# SAMA7D65_MPU.net
KiCad netlist of a schematic drawn in Altium Designer
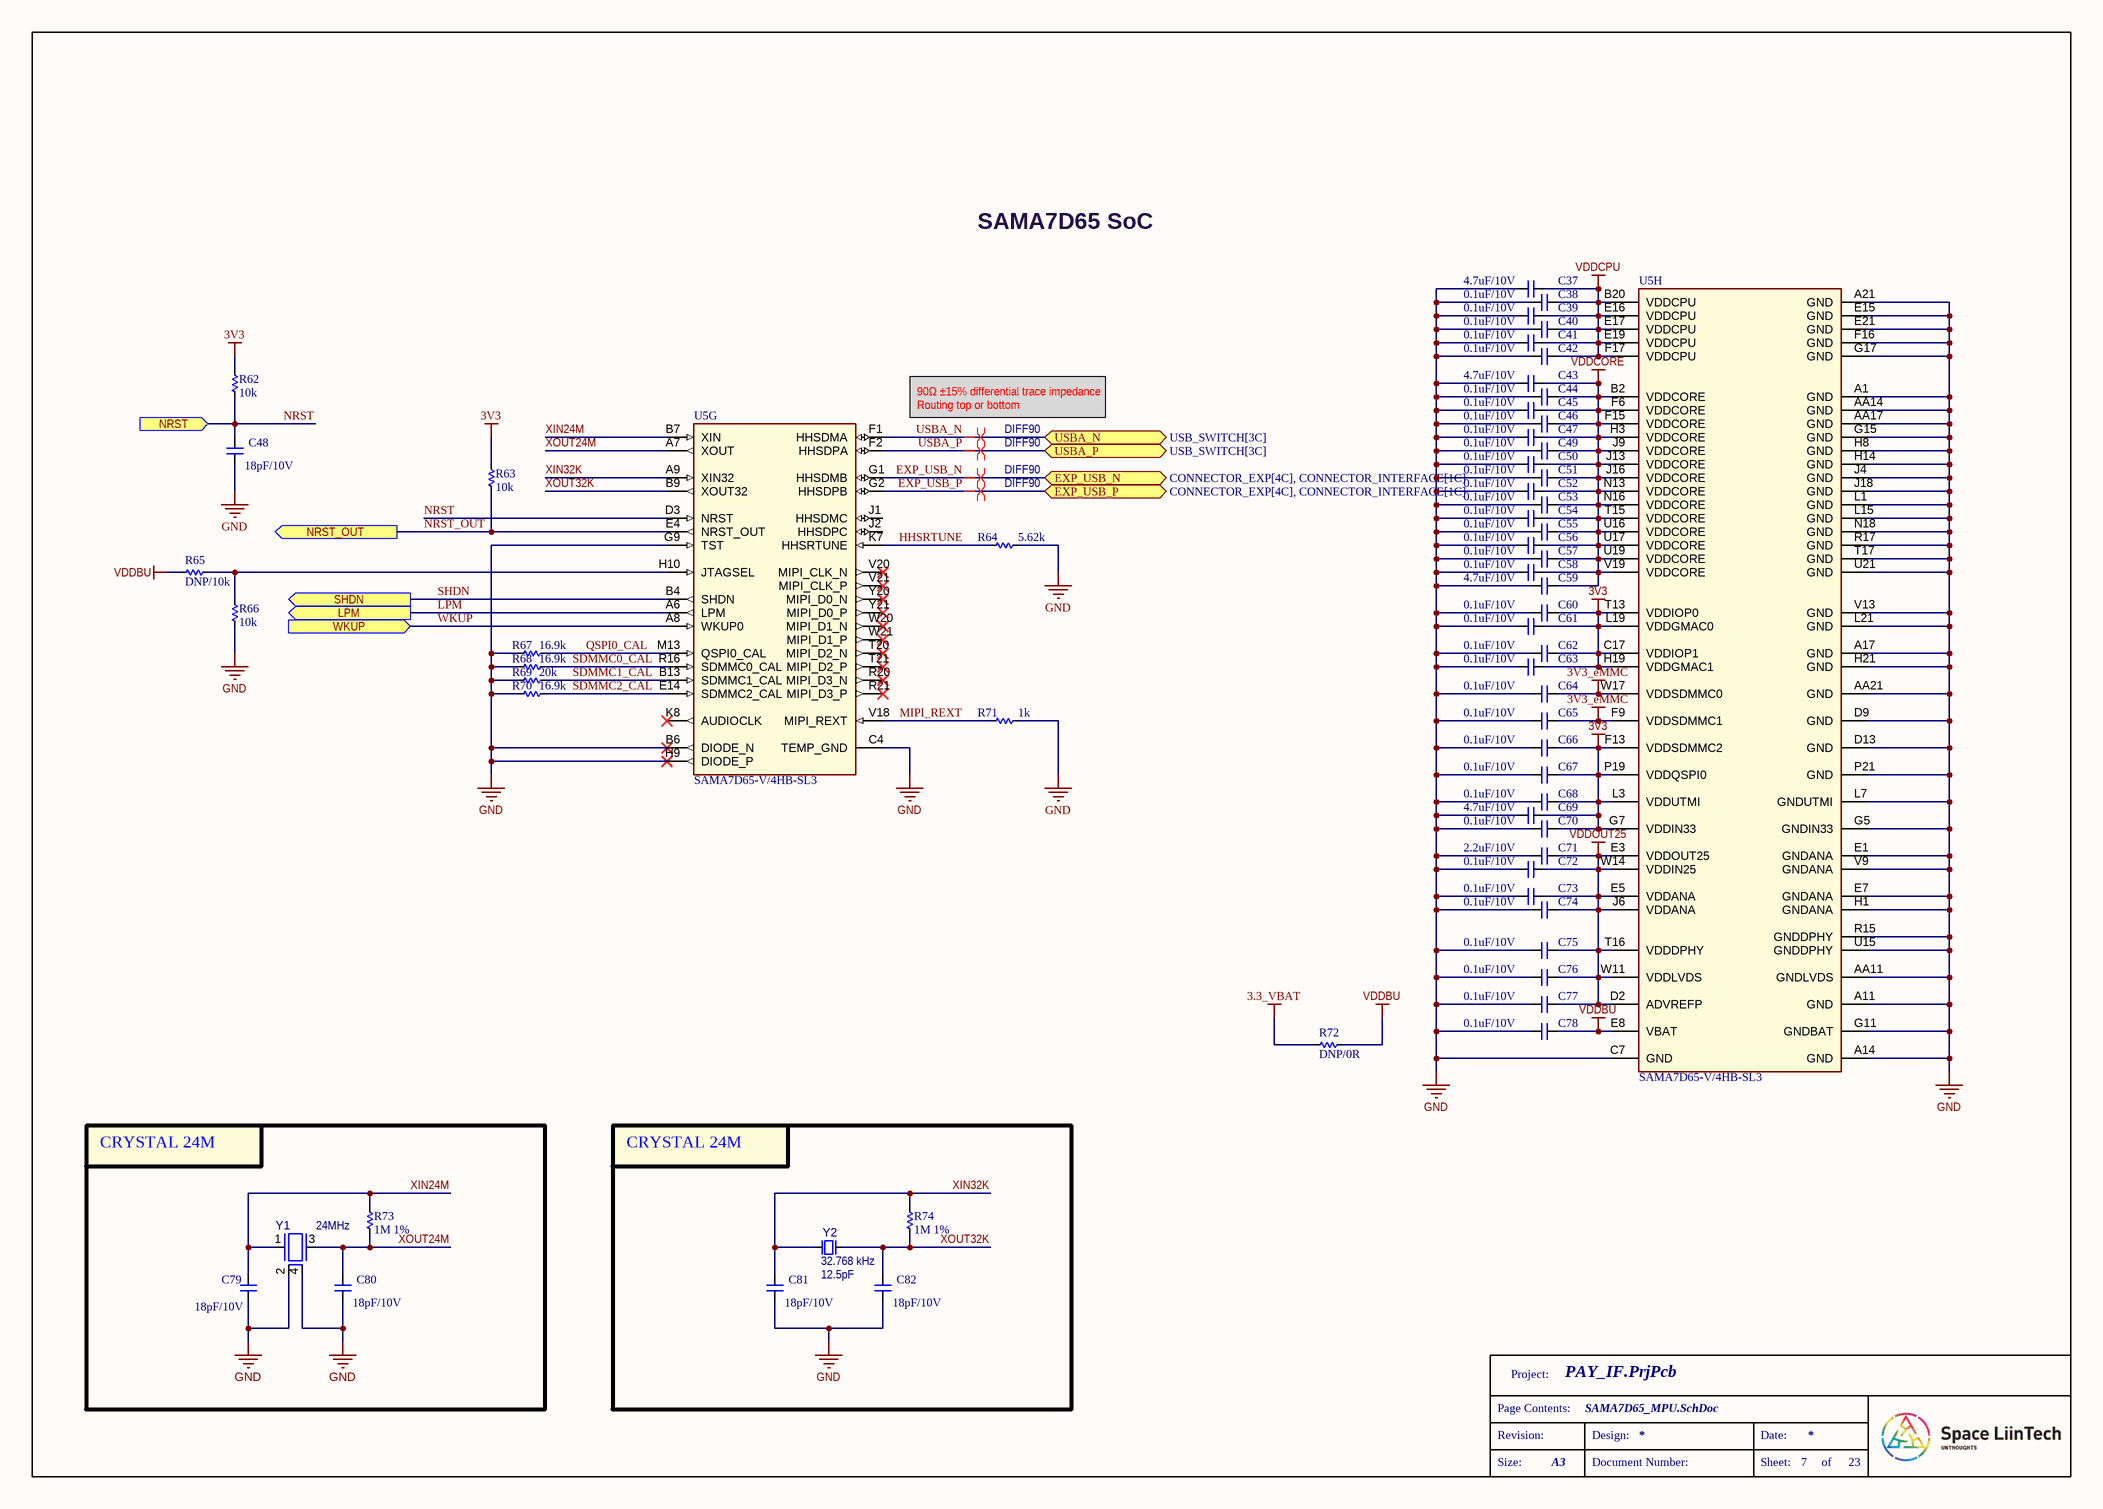
[diagram p0: SAMA7D65_MPU.SchDoc]

(export (version "E")
  (design (tool "Eeschema 10.0.6"))
  (components
    (comp (ref "C37")
      (value "4.7uF/10V")
      (footprint "CAP_C_1005X50_L")
      (description "CAP CHIP")
      (libsource (lib "IFBschelib") (part "_CAP_C_2"))
    )
    (comp (ref "C38")
      (value "0.1uF/10V")
      (footprint "CAP_C_0603x30")
      (description "CAP CHIP")
      (libsource (lib "IFBschelib") (part "_CAP_C_2"))
    )
    (comp (ref "C39")
      (value "0.1uF/10V")
      (footprint "CAP_C_0603x30")
      (description "CAP CHIP")
      (libsource (lib "IFBschelib") (part "_CAP_C_2"))
    )
    (comp (ref "C40")
      (value "0.1uF/10V")
      (footprint "CAP_C_0603x30")
      (description "CAP CHIP")
      (libsource (lib "IFBschelib") (part "_CAP_C_2"))
    )
    (comp (ref "C41")
      (value "0.1uF/10V")
      (footprint "CAP_C_0603x30")
      (description "CAP CHIP")
      (libsource (lib "IFBschelib") (part "_CAP_C_2"))
    )
    (comp (ref "C42")
      (value "0.1uF/10V")
      (footprint "CAP_C_0603x30")
      (description "CAP CHIP")
      (libsource (lib "IFBschelib") (part "_CAP_C_2"))
    )
    (comp (ref "C43")
      (value "4.7uF/10V")
      (footprint "CAP_C_1005X50_L")
      (description "CAP CHIP")
      (libsource (lib "IFBschelib") (part "_CAP_C_2"))
    )
    (comp (ref "C44")
      (value "0.1uF/10V")
      (footprint "CAP_C_0603x30")
      (description "CAP CHIP")
      (libsource (lib "IFBschelib") (part "_CAP_C_2"))
    )
    (comp (ref "C45")
      (value "0.1uF/10V")
      (footprint "CAP_C_0603x30")
      (description "CAP CHIP")
      (libsource (lib "IFBschelib") (part "_CAP_C_2"))
    )
    (comp (ref "C46")
      (value "0.1uF/10V")
      (footprint "CAP_C_0603x30")
      (description "CAP CHIP")
      (libsource (lib "IFBschelib") (part "_CAP_C_2"))
    )
    (comp (ref "C47")
      (value "0.1uF/10V")
      (footprint "CAP_C_0603x30")
      (description "CAP CHIP")
      (libsource (lib "IFBschelib") (part "_CAP_C_2"))
    )
    (comp (ref "C48")
      (value "18pF/10V")
      (footprint "CAP_C_0603x30")
      (description "CAP CHIP")
      (libsource (lib "IFBschelib") (part "_CAP_C_2"))
    )
    (comp (ref "C49")
      (value "0.1uF/10V")
      (footprint "CAP_C_0603x30")
      (description "CAP CHIP")
      (libsource (lib "IFBschelib") (part "_CAP_C_2"))
    )
    (comp (ref "C50")
      (value "0.1uF/10V")
      (footprint "CAP_C_0603x30")
      (description "CAP CHIP")
      (libsource (lib "IFBschelib") (part "_CAP_C_2"))
    )
    (comp (ref "C51")
      (value "0.1uF/10V")
      (footprint "CAP_C_0603x30")
      (description "CAP CHIP")
      (libsource (lib "IFBschelib") (part "_CAP_C_2"))
    )
    (comp (ref "C52")
      (value "0.1uF/10V")
      (footprint "CAP_C_0603x30")
      (description "CAP CHIP")
      (libsource (lib "IFBschelib") (part "_CAP_C_2"))
    )
    (comp (ref "C53")
      (value "0.1uF/10V")
      (footprint "CAP_C_0603x30")
      (description "CAP CHIP")
      (libsource (lib "IFBschelib") (part "_CAP_C_2"))
    )
    (comp (ref "C54")
      (value "0.1uF/10V")
      (footprint "CAP_C_0603x30")
      (description "CAP CHIP")
      (libsource (lib "IFBschelib") (part "_CAP_C_2"))
    )
    (comp (ref "C55")
      (value "0.1uF/10V")
      (footprint "CAP_C_0603x30")
      (description "CAP CHIP")
      (libsource (lib "IFBschelib") (part "_CAP_C_2"))
    )
    (comp (ref "C56")
      (value "0.1uF/10V")
      (footprint "CAP_C_0603x30")
      (description "CAP CHIP")
      (libsource (lib "IFBschelib") (part "_CAP_C_2"))
    )
    (comp (ref "C57")
      (value "0.1uF/10V")
      (footprint "CAP_C_0603x30")
      (description "CAP CHIP")
      (libsource (lib "IFBschelib") (part "_CAP_C_2"))
    )
    (comp (ref "C58")
      (value "0.1uF/10V")
      (footprint "CAP_C_0603x30")
      (description "CAP CHIP")
      (libsource (lib "IFBschelib") (part "_CAP_C_2"))
    )
    (comp (ref "C59")
      (value "4.7uF/10V")
      (footprint "CAP_C_1005X50_L")
      (description "CAP CHIP")
      (libsource (lib "IFBschelib") (part "_CAP_C_2"))
    )
    (comp (ref "C60")
      (value "0.1uF/10V")
      (footprint "CAP_C_0603x30")
      (description "CAP CHIP")
      (libsource (lib "IFBschelib") (part "_CAP_C_2"))
    )
    (comp (ref "C61")
      (value "0.1uF/10V")
      (footprint "CAP_C_0603x30")
      (description "CAP CHIP")
      (libsource (lib "IFBschelib") (part "_CAP_C_2"))
    )
    (comp (ref "C62")
      (value "0.1uF/10V")
      (footprint "CAP_C_0603x30")
      (description "CAP CHIP")
      (libsource (lib "IFBschelib") (part "_CAP_C_2"))
    )
    (comp (ref "C63")
      (value "0.1uF/10V")
      (footprint "CAP_C_0603x30")
      (description "CAP CHIP")
      (libsource (lib "IFBschelib") (part "_CAP_C_2"))
    )
    (comp (ref "C64")
      (value "0.1uF/10V")
      (footprint "CAP_C_0603x30")
      (description "CAP CHIP")
      (libsource (lib "IFBschelib") (part "_CAP_C_2"))
    )
    (comp (ref "C65")
      (value "0.1uF/10V")
      (footprint "CAP_C_0603x30")
      (description "CAP CHIP")
      (libsource (lib "IFBschelib") (part "_CAP_C_2"))
    )
    (comp (ref "C66")
      (value "0.1uF/10V")
      (footprint "CAP_C_0603x30")
      (description "CAP CHIP")
      (libsource (lib "IFBschelib") (part "_CAP_C_2"))
    )
    (comp (ref "C67")
      (value "0.1uF/10V")
      (footprint "CAP_C_0603x30")
      (description "CAP CHIP")
      (libsource (lib "IFBschelib") (part "_CAP_C_2"))
    )
    (comp (ref "C68")
      (value "0.1uF/10V")
      (footprint "CAP_C_0603x30")
      (description "CAP CHIP")
      (libsource (lib "IFBschelib") (part "_CAP_C_2"))
    )
    (comp (ref "C69")
      (value "4.7uF/10V")
      (footprint "CAP_C_1005X50_L")
      (description "CAP CHIP")
      (libsource (lib "IFBschelib") (part "_CAP_C_2"))
    )
    (comp (ref "C70")
      (value "0.1uF/10V")
      (footprint "CAP_C_0603x30")
      (description "CAP CHIP")
      (libsource (lib "IFBschelib") (part "_CAP_C_2"))
    )
    (comp (ref "C71")
      (value "2.2uF/10V")
      (footprint "CAP_C_1005X50_L")
      (description "CAP CHIP")
      (libsource (lib "IFBschelib") (part "_CAP_C_2"))
    )
    (comp (ref "C72")
      (value "0.1uF/10V")
      (footprint "CAP_C_0603x30")
      (description "CAP CHIP")
      (libsource (lib "IFBschelib") (part "_CAP_C_2"))
    )
    (comp (ref "C73")
      (value "0.1uF/10V")
      (footprint "CAP_C_0603x30")
      (description "CAP CHIP")
      (libsource (lib "IFBschelib") (part "_CAP_C_2"))
    )
    (comp (ref "C74")
      (value "0.1uF/10V")
      (footprint "CAP_C_0603x30")
      (description "CAP CHIP")
      (libsource (lib "IFBschelib") (part "_CAP_C_2"))
    )
    (comp (ref "C75")
      (value "0.1uF/10V")
      (footprint "CAP_C_0603x30")
      (description "CAP CHIP")
      (libsource (lib "IFBschelib") (part "_CAP_C_2"))
    )
    (comp (ref "C76")
      (value "0.1uF/10V")
      (footprint "CAP_C_0603x30")
      (description "CAP CHIP")
      (libsource (lib "IFBschelib") (part "_CAP_C_2"))
    )
    (comp (ref "C77")
      (value "0.1uF/10V")
      (footprint "CAP_C_0603x30")
      (description "CAP CHIP")
      (libsource (lib "IFBschelib") (part "_CAP_C_2"))
    )
    (comp (ref "C78")
      (value "0.1uF/10V")
      (footprint "CAP_C_0603x30")
      (description "CAP CHIP")
      (libsource (lib "IFBschelib") (part "_CAP_C_2"))
    )
    (comp (ref "C79")
      (value "18pF/10V")
      (footprint "CAP_C_0603x30")
      (description "CAP CHIP")
      (libsource (lib "IFBschelib") (part "_CAP_C_2"))
    )
    (comp (ref "C80")
      (value "18pF/10V")
      (footprint "CAP_C_0603x30")
      (description "CAP CHIP")
      (libsource (lib "IFBschelib") (part "_CAP_C_2"))
    )
    (comp (ref "C81")
      (value "18pF/10V")
      (footprint "CAP_C_0603x30")
      (description "CAP CHIP")
      (libsource (lib "IFBschelib") (part "_CAP_C_2"))
    )
    (comp (ref "C82")
      (value "18pF/10V")
      (footprint "CAP_C_0603x30")
      (description "CAP CHIP")
      (libsource (lib "IFBschelib") (part "_CAP_C_2"))
    )
    (comp (ref "R62")
      (value "10k")
      (footprint "RES_C_1005x30_L")
      (description "RES")
      (libsource (lib "IFBschelib") (part "_RES_B_2"))
    )
    (comp (ref "R63")
      (value "10k")
      (footprint "RES_C_1005x30_L")
      (description "RES")
      (libsource (lib "IFBschelib") (part "_RES_B_2"))
    )
    (comp (ref "R64")
      (value "5.62k")
      (footprint "RES_C_1005x30_L")
      (description "RES")
      (libsource (lib "IFBschelib") (part "_RES_B_2"))
    )
    (comp (ref "R65")
      (value "DNP/10k")
      (footprint "RES_C_1005x30_L")
      (description "RES")
      (libsource (lib "IFBschelib") (part "_RES_B_2"))
    )
    (comp (ref "R66")
      (value "10k")
      (footprint "RES_C_1005x30_L")
      (description "RES")
      (libsource (lib "IFBschelib") (part "_RES_B_2"))
    )
    (comp (ref "R67")
      (value "16.9k")
      (footprint "RES_C_0603X30")
      (description "RES")
      (libsource (lib "IFBschelib") (part "_RES_B_2"))
    )
    (comp (ref "R68")
      (value "16.9k")
      (footprint "RES_C_0603X30")
      (description "RES")
      (libsource (lib "IFBschelib") (part "_RES_B_2"))
    )
    (comp (ref "R69")
      (value "20k")
      (footprint "RES_C_0603X30")
      (description "RES")
      (libsource (lib "IFBschelib") (part "_RES_B_2"))
    )
    (comp (ref "R70")
      (value "16.9k")
      (footprint "RES_C_0603X30")
      (description "RES")
      (libsource (lib "IFBschelib") (part "_RES_B_2"))
    )
    (comp (ref "R71")
      (value "1k")
      (footprint "RES_C_1005x30_L")
      (description "RES")
      (libsource (lib "IFBschelib") (part "_RES_B_2"))
    )
    (comp (ref "R72")
      (value "DNP/0R")
      (footprint "RES_C_1005x30_L")
      (description "RES")
      (libsource (lib "IFBschelib") (part "_RES_B_2"))
    )
    (comp (ref "R73")
      (value "1M 1%")
      (footprint "RES_C_1005x30_L")
      (description "RES")
      (libsource (lib "IFBschelib") (part "_RES_B_2"))
    )
    (comp (ref "R74")
      (value "1M 1%")
      (footprint "RES_C_1005x30_L")
      (description "RES")
      (libsource (lib "IFBschelib") (part "_RES_B_2"))
    )
    (comp (ref "U5")
      (value "SAMA7D65-V/4HB-SL3")
      (footprint "TFBGA-343_14x14")
      (description "SAMA7D65 MPU 1000MHz Cortex-A7 TFBGA-343")
      (fields (field (name "Comment") "SAMA7D65") (field (name "OWNER") "Ciprian Abramov"))
      (libsource (lib "IFBschelib") (part "SAMA7D65"))
    )
    (comp (ref "Y1")
      (value "24MHz")
      (footprint "XTAL_ECS2401037B2JTNTR")
      (description "CRYSTAL 24 MHZ 10PF SMD")
      (fields
        (field (name "TOLERANCE") "20ppm")
        (field (name "Comment") "Crystal 4 Pins")
        (field (name "OWNER") "Ciprian Abramov")
      )
      (libsource (lib "IFBschelib") (part "ECS-240-10-37B2-JTN-TR"))
    )
    (comp (ref "Y2")
      (value "32.768 kHz")
      (footprint "CRYSTAL_FC-12M_L2.05W1.2H0.6")
      (description "CRYSTAL 32.7680KHZ 12.5PF SMD")
      (fields
        (field (name "TOLERANCE") "20ppm")
        (field (name "LOAD CAPACITANCE") "12.5pF")
        (field (name "Comment") "Crystal 2 Pins")
        (field (name "OWNER") "Dragos Danaila")
      )
      (libsource (lib "IFBschelib") (part "FC-12M 32.7680KA-A3"))
    )
  )
  (nets
    (net (code "1") (name "/EXP_USB_N") (class "Default")
      (node (ref "U5") (pin "G1") (pinfunction "HHSDMB_G1") (pintype "bidirectional"))
    )
    (net (code "2") (name "/EXP_USB_P") (class "Default")
      (node (ref "U5") (pin "G2") (pinfunction "HHSDPB_G2") (pintype "bidirectional"))
    )
    (net (code "3") (name "/HHSRTUNE") (class "Default")
      (node (ref "R64") (pin "1") (pinfunction "1_1") (pintype "passive"))
      (node (ref "U5") (pin "K7") (pinfunction "HHSRTUNE_K7") (pintype "input"))
    )
    (net (code "4") (name "/LPM") (class "Default")
      (node (ref "U5") (pin "A6") (pinfunction "LPM_A6") (pintype "output"))
    )
    (net (code "5") (name "/MIPI_REXT") (class "Default")
      (node (ref "R71") (pin "1") (pinfunction "1_1") (pintype "passive"))
      (node (ref "U5") (pin "V18") (pinfunction "MIPI_REXT_V18") (pintype "input"))
    )
    (net (code "6") (name "/NRST") (class "Default")
      (node (ref "C48") (pin "1") (pinfunction "1_1") (pintype "passive"))
      (node (ref "R62") (pin "2") (pinfunction "2_2") (pintype "passive"))
      (node (ref "U5") (pin "D3") (pinfunction "NRST_D3") (pintype "input"))
    )
    (net (code "7") (name "/NRST_OUT") (class "Default")
      (node (ref "R63") (pin "2") (pinfunction "2_2") (pintype "passive"))
      (node (ref "U5") (pin "E4") (pinfunction "NRST_OUT_E4") (pintype "output"))
    )
    (net (code "8") (name "/QSPI0_CAL") (class "Default")
      (node (ref "R67") (pin "2") (pinfunction "2_2") (pintype "passive"))
      (node (ref "U5") (pin "M13") (pinfunction "QSPI0_CAL_M13") (pintype "input"))
    )
    (net (code "9") (name "/SDMMC0_CAL") (class "Default")
      (node (ref "R68") (pin "2") (pinfunction "2_2") (pintype "passive"))
      (node (ref "U5") (pin "R16") (pinfunction "SDMMC0_CAL_R16") (pintype "input"))
    )
    (net (code "10") (name "/SDMMC1_CAL") (class "Default")
      (node (ref "R69") (pin "2") (pinfunction "2_2") (pintype "passive"))
      (node (ref "U5") (pin "B13") (pinfunction "SDMMC1_CAL_B13") (pintype "input"))
    )
    (net (code "11") (name "/SDMMC2_CAL") (class "Default")
      (node (ref "R70") (pin "2") (pinfunction "2_2") (pintype "passive"))
      (node (ref "U5") (pin "E14") (pinfunction "SDMMC2_CAL_E14") (pintype "input"))
    )
    (net (code "12") (name "/SHDN") (class "Default")
      (node (ref "U5") (pin "B4") (pinfunction "SHDN_B4") (pintype "output"))
    )
    (net (code "13") (name "/USBA_N") (class "Default")
      (node (ref "U5") (pin "F1") (pinfunction "HHSDMA_F1") (pintype "bidirectional"))
    )
    (net (code "14") (name "/USBA_P") (class "Default")
      (node (ref "U5") (pin "F2") (pinfunction "HHSDPA_F2") (pintype "bidirectional"))
    )
    (net (code "15") (name "/WKUP") (class "Default")
      (node (ref "U5") (pin "A8") (pinfunction "WKUP0_A8") (pintype "input"))
    )
    (net (code "16") (name "/XIN24M") (class "Default")
      (node (ref "C79") (pin "1") (pinfunction "1_1") (pintype "passive"))
      (node (ref "R73") (pin "2") (pinfunction "2_2") (pintype "passive"))
      (node (ref "U5") (pin "B7") (pinfunction "XIN_B7") (pintype "input"))
      (node (ref "Y1") (pin "1") (pinfunction "Osc1_1") (pintype "passive"))
    )
    (net (code "17") (name "/XIN32K") (class "Default")
      (node (ref "C81") (pin "1") (pinfunction "1_1") (pintype "passive"))
      (node (ref "R74") (pin "2") (pinfunction "2_2") (pintype "passive"))
      (node (ref "U5") (pin "A9") (pinfunction "XIN32_A9") (pintype "input"))
      (node (ref "Y2") (pin "1") (pinfunction "Osc1_1") (pintype "passive"))
    )
    (net (code "18") (name "/XOUT24M") (class "Default")
      (node (ref "C80") (pin "1") (pinfunction "1_1") (pintype "passive"))
      (node (ref "R73") (pin "1") (pinfunction "1_1") (pintype "passive"))
      (node (ref "U5") (pin "A7") (pinfunction "XOUT_A7") (pintype "output"))
      (node (ref "Y1") (pin "3") (pinfunction "Osc2_3") (pintype "passive"))
    )
    (net (code "19") (name "/XOUT32K") (class "Default")
      (node (ref "C82") (pin "1") (pinfunction "1_1") (pintype "passive"))
      (node (ref "R74") (pin "1") (pinfunction "1_1") (pintype "passive"))
      (node (ref "U5") (pin "B9") (pinfunction "XOUT32_B9") (pintype "output"))
      (node (ref "Y2") (pin "2") (pinfunction "Osc2_2") (pintype "passive"))
    )
    (net (code "20") (name "3.3_VBAT") (class "Default")
      (node (ref "R72") (pin "1") (pinfunction "1_1") (pintype "passive"))
    )
    (net (code "21") (name "3V3") (class "Default")
      (node (ref "C60") (pin "2") (pinfunction "2_2") (pintype "passive"))
      (node (ref "C61") (pin "2") (pinfunction "2_2") (pintype "passive"))
      (node (ref "C62") (pin "2") (pinfunction "2_2") (pintype "passive"))
      (node (ref "C63") (pin "2") (pinfunction "2_2") (pintype "passive"))
      (node (ref "C66") (pin "2") (pinfunction "2_2") (pintype "passive"))
      (node (ref "C67") (pin "2") (pinfunction "2_2") (pintype "passive"))
      (node (ref "C68") (pin "2") (pinfunction "2_2") (pintype "passive"))
      (node (ref "C69") (pin "2") (pinfunction "2_2") (pintype "passive"))
      (node (ref "C70") (pin "2") (pinfunction "2_2") (pintype "passive"))
      (node (ref "R62") (pin "1") (pinfunction "1_1") (pintype "passive"))
      (node (ref "R63") (pin "1") (pinfunction "1_1") (pintype "passive"))
      (node (ref "U5") (pin "C17") (pinfunction "VDDIOP1_C17") (pintype "power_in"))
      (node (ref "U5") (pin "F13") (pinfunction "VDDSDMMC2_F13") (pintype "power_in"))
      (node (ref "U5") (pin "G7") (pinfunction "VDDIN33_G7") (pintype "power_in"))
      (node (ref "U5") (pin "H19") (pinfunction "VDDGMAC1_H19") (pintype "power_in"))
      (node (ref "U5") (pin "L19") (pinfunction "VDDGMAC0_L19") (pintype "power_in"))
      (node (ref "U5") (pin "L3") (pinfunction "VDDUTMI_L3") (pintype "power_in"))
      (node (ref "U5") (pin "P19") (pinfunction "VDDQSPI0_P19") (pintype "power_in"))
      (node (ref "U5") (pin "T13") (pinfunction "VDDIOP0_T13") (pintype "power_in"))
    )
    (net (code "22") (name "3V3_eMMC") (class "Default")
      (node (ref "C64") (pin "2") (pinfunction "2_2") (pintype "passive"))
      (node (ref "C65") (pin "2") (pinfunction "2_2") (pintype "passive"))
      (node (ref "U5") (pin "F9") (pinfunction "VDDSDMMC1_F9") (pintype "power_in"))
      (node (ref "U5") (pin "W17") (pinfunction "VDDSDMMC0_W17") (pintype "power_in"))
    )
    (net (code "23") (name "GND") (class "Default")
      (node (ref "C37") (pin "1") (pinfunction "1_1") (pintype "passive"))
      (node (ref "C38") (pin "1") (pinfunction "1_1") (pintype "passive"))
      (node (ref "C39") (pin "1") (pinfunction "1_1") (pintype "passive"))
      (node (ref "C40") (pin "1") (pinfunction "1_1") (pintype "passive"))
      (node (ref "C41") (pin "1") (pinfunction "1_1") (pintype "passive"))
      (node (ref "C42") (pin "1") (pinfunction "1_1") (pintype "passive"))
      (node (ref "C43") (pin "1") (pinfunction "1_1") (pintype "passive"))
      (node (ref "C44") (pin "1") (pinfunction "1_1") (pintype "passive"))
      (node (ref "C45") (pin "1") (pinfunction "1_1") (pintype "passive"))
      (node (ref "C46") (pin "1") (pinfunction "1_1") (pintype "passive"))
      (node (ref "C47") (pin "1") (pinfunction "1_1") (pintype "passive"))
      (node (ref "C48") (pin "2") (pinfunction "2_2") (pintype "passive"))
      (node (ref "C49") (pin "1") (pinfunction "1_1") (pintype "passive"))
      (node (ref "C50") (pin "1") (pinfunction "1_1") (pintype "passive"))
      (node (ref "C51") (pin "1") (pinfunction "1_1") (pintype "passive"))
      (node (ref "C52") (pin "1") (pinfunction "1_1") (pintype "passive"))
      (node (ref "C53") (pin "1") (pinfunction "1_1") (pintype "passive"))
      (node (ref "C54") (pin "1") (pinfunction "1_1") (pintype "passive"))
      (node (ref "C55") (pin "1") (pinfunction "1_1") (pintype "passive"))
      (node (ref "C56") (pin "1") (pinfunction "1_1") (pintype "passive"))
      (node (ref "C57") (pin "1") (pinfunction "1_1") (pintype "passive"))
      (node (ref "C58") (pin "1") (pinfunction "1_1") (pintype "passive"))
      (node (ref "C59") (pin "1") (pinfunction "1_1") (pintype "passive"))
      (node (ref "C60") (pin "1") (pinfunction "1_1") (pintype "passive"))
      (node (ref "C61") (pin "1") (pinfunction "1_1") (pintype "passive"))
      (node (ref "C62") (pin "1") (pinfunction "1_1") (pintype "passive"))
      (node (ref "C63") (pin "1") (pinfunction "1_1") (pintype "passive"))
      (node (ref "C64") (pin "1") (pinfunction "1_1") (pintype "passive"))
      (node (ref "C65") (pin "1") (pinfunction "1_1") (pintype "passive"))
      (node (ref "C66") (pin "1") (pinfunction "1_1") (pintype "passive"))
      (node (ref "C67") (pin "1") (pinfunction "1_1") (pintype "passive"))
      (node (ref "C68") (pin "1") (pinfunction "1_1") (pintype "passive"))
      (node (ref "C69") (pin "1") (pinfunction "1_1") (pintype "passive"))
      (node (ref "C70") (pin "1") (pinfunction "1_1") (pintype "passive"))
      (node (ref "C71") (pin "1") (pinfunction "1_1") (pintype "passive"))
      (node (ref "C72") (pin "1") (pinfunction "1_1") (pintype "passive"))
      (node (ref "C73") (pin "1") (pinfunction "1_1") (pintype "passive"))
      (node (ref "C74") (pin "1") (pinfunction "1_1") (pintype "passive"))
      (node (ref "C75") (pin "1") (pinfunction "1_1") (pintype "passive"))
      (node (ref "C76") (pin "1") (pinfunction "1_1") (pintype "passive"))
      (node (ref "C77") (pin "1") (pinfunction "1_1") (pintype "passive"))
      (node (ref "C78") (pin "1") (pinfunction "1_1") (pintype "passive"))
      (node (ref "C79") (pin "2") (pinfunction "2_2") (pintype "passive"))
      (node (ref "C80") (pin "2") (pinfunction "2_2") (pintype "passive"))
      (node (ref "C81") (pin "2") (pinfunction "2_2") (pintype "passive"))
      (node (ref "C82") (pin "2") (pinfunction "2_2") (pintype "passive"))
      (node (ref "R64") (pin "2") (pinfunction "2_2") (pintype "passive"))
      (node (ref "R66") (pin "1") (pinfunction "1_1") (pintype "passive"))
      (node (ref "R67") (pin "1") (pinfunction "1_1") (pintype "passive"))
      (node (ref "R68") (pin "1") (pinfunction "1_1") (pintype "passive"))
      (node (ref "R69") (pin "1") (pinfunction "1_1") (pintype "passive"))
      (node (ref "R70") (pin "1") (pinfunction "1_1") (pintype "passive"))
      (node (ref "R71") (pin "2") (pinfunction "2_2") (pintype "passive"))
      (node (ref "U5") (pin "A1") (pinfunction "GND_A1") (pintype "power_in"))
      (node (ref "U5") (pin "A11") (pinfunction "GND_A11") (pintype "power_in"))
      (node (ref "U5") (pin "A14") (pinfunction "GND_A14") (pintype "power_in"))
      (node (ref "U5") (pin "A17") (pinfunction "GND_A17") (pintype "power_in"))
      (node (ref "U5") (pin "A21") (pinfunction "GND_A21") (pintype "power_in"))
      (node (ref "U5") (pin "AA11") (pinfunction "GNDLVDS_AA11") (pintype "power_in"))
      (node (ref "U5") (pin "AA14") (pinfunction "GND_AA14") (pintype "power_in"))
      (node (ref "U5") (pin "AA17") (pinfunction "GND_AA17") (pintype "power_in"))
      (node (ref "U5") (pin "AA21") (pinfunction "GND_AA21") (pintype "power_in"))
      (node (ref "U5") (pin "B6") (pinfunction "DIODE_N_B6") (pintype "output"))
      (node (ref "U5") (pin "C4") (pinfunction "TEMP_GND_C4") (pintype "passive"))
      (node (ref "U5") (pin "C7") (pinfunction "GND_C7") (pintype "power_in"))
      (node (ref "U5") (pin "D13") (pinfunction "GND_D13") (pintype "power_in"))
      (node (ref "U5") (pin "D9") (pinfunction "GND_D9") (pintype "power_in"))
      (node (ref "U5") (pin "E1") (pinfunction "GNDANA_E1") (pintype "power_in"))
      (node (ref "U5") (pin "E15") (pinfunction "GND_E15") (pintype "power_in"))
      (node (ref "U5") (pin "E21") (pinfunction "GND_E21") (pintype "power_in"))
      (node (ref "U5") (pin "E7") (pinfunction "GNDANA_E7") (pintype "power_in"))
      (node (ref "U5") (pin "F16") (pinfunction "GND_F16") (pintype "power_in"))
      (node (ref "U5") (pin "G11") (pinfunction "GNDBAT_G11") (pintype "power_in"))
      (node (ref "U5") (pin "G15") (pinfunction "GND_G15") (pintype "power_in"))
      (node (ref "U5") (pin "G17") (pinfunction "GND_G17") (pintype "power_in"))
      (node (ref "U5") (pin "G5") (pinfunction "GNDIN33_G5") (pintype "power_in"))
      (node (ref "U5") (pin "G9") (pinfunction "TST_G9") (pintype "input"))
      (node (ref "U5") (pin "H1") (pinfunction "GNDANA_H1") (pintype "power_in"))
      (node (ref "U5") (pin "H14") (pinfunction "GND_H14") (pintype "power_in"))
      (node (ref "U5") (pin "H21") (pinfunction "GND_H21") (pintype "power_in"))
      (node (ref "U5") (pin "H8") (pinfunction "GND_H8") (pintype "power_in"))
      (node (ref "U5") (pin "H9") (pinfunction "DIODE_P_H9") (pintype "output"))
      (node (ref "U5") (pin "J18") (pinfunction "GND_J18") (pintype "power_in"))
      (node (ref "U5") (pin "J4") (pinfunction "GND_J4") (pintype "power_in"))
      (node (ref "U5") (pin "L1") (pinfunction "GND_L1") (pintype "power_in"))
      (node (ref "U5") (pin "L15") (pinfunction "GND_L15") (pintype "power_in"))
      (node (ref "U5") (pin "L21") (pinfunction "GND_L21") (pintype "power_in"))
      (node (ref "U5") (pin "L7") (pinfunction "GNDUTMI_L7") (pintype "power_in"))
      (node (ref "U5") (pin "N18") (pinfunction "GND_N18") (pintype "power_in"))
      (node (ref "U5") (pin "P21") (pinfunction "GND_P21") (pintype "power_in"))
      (node (ref "U5") (pin "R15") (pinfunction "GNDDPHY_R15") (pintype "power_in"))
      (node (ref "U5") (pin "R17") (pinfunction "GND_R17") (pintype "power_in"))
      (node (ref "U5") (pin "T17") (pinfunction "GND_T17") (pintype "power_in"))
      (node (ref "U5") (pin "U15") (pinfunction "GNDDPHY_U15") (pintype "power_in"))
      (node (ref "U5") (pin "U21") (pinfunction "GND_U21") (pintype "power_in"))
      (node (ref "U5") (pin "V13") (pinfunction "GND_V13") (pintype "power_in"))
      (node (ref "U5") (pin "V9") (pinfunction "GNDANA_V9") (pintype "power_in"))
      (node (ref "Y1") (pin "2") (pinfunction "GND_2") (pintype "power_in"))
      (node (ref "Y1") (pin "4") (pinfunction "GND_4") (pintype "power_in"))
    )
    (net (code "24") (name "Net-(U5G-JTAGSEL)") (class "Default")
      (node (ref "R65") (pin "1") (pinfunction "1_1") (pintype "passive"))
      (node (ref "R66") (pin "2") (pinfunction "2_2") (pintype "passive"))
      (node (ref "U5") (pin "H10") (pinfunction "JTAGSEL_H10") (pintype "input"))
    )
    (net (code "25") (name "VDDBU") (class "Default")
      (node (ref "C78") (pin "2") (pinfunction "2_2") (pintype "passive"))
      (node (ref "R65") (pin "2") (pinfunction "2_2") (pintype "passive"))
      (node (ref "R72") (pin "2") (pinfunction "2_2") (pintype "passive"))
      (node (ref "U5") (pin "E8") (pinfunction "VBAT_E8") (pintype "power_in"))
    )
    (net (code "26") (name "VDDCORE") (class "Default")
      (node (ref "C43") (pin "2") (pinfunction "2_2") (pintype "passive"))
      (node (ref "C44") (pin "2") (pinfunction "2_2") (pintype "passive"))
      (node (ref "C45") (pin "2") (pinfunction "2_2") (pintype "passive"))
      (node (ref "C46") (pin "2") (pinfunction "2_2") (pintype "passive"))
      (node (ref "C47") (pin "2") (pinfunction "2_2") (pintype "passive"))
      (node (ref "C49") (pin "2") (pinfunction "2_2") (pintype "passive"))
      (node (ref "C50") (pin "2") (pinfunction "2_2") (pintype "passive"))
      (node (ref "C51") (pin "2") (pinfunction "2_2") (pintype "passive"))
      (node (ref "C52") (pin "2") (pinfunction "2_2") (pintype "passive"))
      (node (ref "C53") (pin "2") (pinfunction "2_2") (pintype "passive"))
      (node (ref "C54") (pin "2") (pinfunction "2_2") (pintype "passive"))
      (node (ref "C55") (pin "2") (pinfunction "2_2") (pintype "passive"))
      (node (ref "C56") (pin "2") (pinfunction "2_2") (pintype "passive"))
      (node (ref "C57") (pin "2") (pinfunction "2_2") (pintype "passive"))
      (node (ref "C58") (pin "2") (pinfunction "2_2") (pintype "passive"))
      (node (ref "C59") (pin "2") (pinfunction "2_2") (pintype "passive"))
      (node (ref "U5") (pin "B2") (pinfunction "VDDCORE_B2") (pintype "power_in"))
      (node (ref "U5") (pin "F15") (pinfunction "VDDCORE_F15") (pintype "power_in"))
      (node (ref "U5") (pin "F6") (pinfunction "VDDCORE_F6") (pintype "power_in"))
      (node (ref "U5") (pin "H3") (pinfunction "VDDCORE_H3") (pintype "power_in"))
      (node (ref "U5") (pin "J13") (pinfunction "VDDCORE_J13") (pintype "power_in"))
      (node (ref "U5") (pin "J16") (pinfunction "VDDCORE_J16") (pintype "power_in"))
      (node (ref "U5") (pin "J9") (pinfunction "VDDCORE_J9") (pintype "power_in"))
      (node (ref "U5") (pin "N13") (pinfunction "VDDCORE_N13") (pintype "power_in"))
      (node (ref "U5") (pin "N16") (pinfunction "VDDCORE_N16") (pintype "power_in"))
      (node (ref "U5") (pin "T15") (pinfunction "VDDCORE_T15") (pintype "power_in"))
      (node (ref "U5") (pin "U16") (pinfunction "VDDCORE_U16") (pintype "power_in"))
      (node (ref "U5") (pin "U17") (pinfunction "VDDCORE_U17") (pintype "power_in"))
      (node (ref "U5") (pin "U19") (pinfunction "VDDCORE_U19") (pintype "power_in"))
      (node (ref "U5") (pin "V19") (pinfunction "VDDCORE_V19") (pintype "power_in"))
    )
    (net (code "27") (name "VDDCPU") (class "Default")
      (node (ref "C37") (pin "2") (pinfunction "2_2") (pintype "passive"))
      (node (ref "C38") (pin "2") (pinfunction "2_2") (pintype "passive"))
      (node (ref "C39") (pin "2") (pinfunction "2_2") (pintype "passive"))
      (node (ref "C40") (pin "2") (pinfunction "2_2") (pintype "passive"))
      (node (ref "C41") (pin "2") (pinfunction "2_2") (pintype "passive"))
      (node (ref "C42") (pin "2") (pinfunction "2_2") (pintype "passive"))
      (node (ref "U5") (pin "B20") (pinfunction "VDDCPU_B20") (pintype "power_in"))
      (node (ref "U5") (pin "E16") (pinfunction "VDDCPU_E16") (pintype "power_in"))
      (node (ref "U5") (pin "E17") (pinfunction "VDDCPU_E17") (pintype "power_in"))
      (node (ref "U5") (pin "E19") (pinfunction "VDDCPU_E19") (pintype "power_in"))
      (node (ref "U5") (pin "F17") (pinfunction "VDDCPU_F17") (pintype "power_in"))
    )
    (net (code "28") (name "VDDOUT25") (class "Default")
      (node (ref "C71") (pin "2") (pinfunction "2_2") (pintype "passive"))
      (node (ref "C72") (pin "2") (pinfunction "2_2") (pintype "passive"))
      (node (ref "C73") (pin "2") (pinfunction "2_2") (pintype "passive"))
      (node (ref "C74") (pin "2") (pinfunction "2_2") (pintype "passive"))
      (node (ref "C75") (pin "2") (pinfunction "2_2") (pintype "passive"))
      (node (ref "C76") (pin "2") (pinfunction "2_2") (pintype "passive"))
      (node (ref "C77") (pin "2") (pinfunction "2_2") (pintype "passive"))
      (node (ref "U5") (pin "D2") (pinfunction "ADVREFP_D2") (pintype "power_in"))
      (node (ref "U5") (pin "E3") (pinfunction "VDDOUT25_E3") (pintype "power_in"))
      (node (ref "U5") (pin "E5") (pinfunction "VDDANA_E5") (pintype "power_in"))
      (node (ref "U5") (pin "J6") (pinfunction "VDDANA_J6") (pintype "power_in"))
      (node (ref "U5") (pin "T16") (pinfunction "VDDDPHY_T16") (pintype "power_in"))
      (node (ref "U5") (pin "W11") (pinfunction "VDDLVDS_W11") (pintype "power_in"))
      (node (ref "U5") (pin "W14") (pinfunction "VDDIN25_W14") (pintype "power_in"))
    )
    (net (code "29") (name "unconnected-(U5G-AUDIOCLK-PadK8)") (class "Default")
      (node (ref "U5") (pin "K8") (pinfunction "AUDIOCLK_K8") (pintype "output+no_connect"))
    )
    (net (code "30") (name "unconnected-(U5G-HHSDMC-PadJ1)") (class "Default")
      (node (ref "U5") (pin "J1") (pinfunction "HHSDMC_J1") (pintype "bidirectional"))
    )
    (net (code "31") (name "unconnected-(U5G-HHSDPC-PadJ2)") (class "Default")
      (node (ref "U5") (pin "J2") (pinfunction "HHSDPC_J2") (pintype "bidirectional"))
    )
    (net (code "32") (name "unconnected-(U5G-MIPI_CLK_N-PadV20)") (class "Default")
      (node (ref "U5") (pin "V20") (pinfunction "MIPI_CLK_N_V20") (pintype "output+no_connect"))
    )
    (net (code "33") (name "unconnected-(U5G-MIPI_CLK_P-PadV21)") (class "Default")
      (node (ref "U5") (pin "V21") (pinfunction "MIPI_CLK_P_V21") (pintype "output+no_connect"))
    )
    (net (code "34") (name "unconnected-(U5G-MIPI_D0_N-PadY20)") (class "Default")
      (node (ref "U5") (pin "Y20") (pinfunction "MIPI_D0_N_Y20") (pintype "output+no_connect"))
    )
    (net (code "35") (name "unconnected-(U5G-MIPI_D0_P-PadY21)") (class "Default")
      (node (ref "U5") (pin "Y21") (pinfunction "MIPI_D0_P_Y21") (pintype "output+no_connect"))
    )
    (net (code "36") (name "unconnected-(U5G-MIPI_D1_N-PadW20)") (class "Default")
      (node (ref "U5") (pin "W20") (pinfunction "MIPI_D1_N_W20") (pintype "output+no_connect"))
    )
    (net (code "37") (name "unconnected-(U5G-MIPI_D1_P-PadW21)") (class "Default")
      (node (ref "U5") (pin "W21") (pinfunction "MIPI_D1_P_W21") (pintype "output+no_connect"))
    )
    (net (code "38") (name "unconnected-(U5G-MIPI_D2_N-PadT20)") (class "Default")
      (node (ref "U5") (pin "T20") (pinfunction "MIPI_D2_N_T20") (pintype "output+no_connect"))
    )
    (net (code "39") (name "unconnected-(U5G-MIPI_D2_P-PadT21)") (class "Default")
      (node (ref "U5") (pin "T21") (pinfunction "MIPI_D2_P_T21") (pintype "output+no_connect"))
    )
    (net (code "40") (name "unconnected-(U5G-MIPI_D3_N-PadR20)") (class "Default")
      (node (ref "U5") (pin "R20") (pinfunction "MIPI_D3_N_R20") (pintype "output+no_connect"))
    )
    (net (code "41") (name "unconnected-(U5G-MIPI_D3_P-PadR21)") (class "Default")
      (node (ref "U5") (pin "R21") (pinfunction "MIPI_D3_P_R21") (pintype "output+no_connect"))
    )
  )
)
